# ScannerControlsBreakout.net
KiCad netlist of a schematic drawn in EAGLE
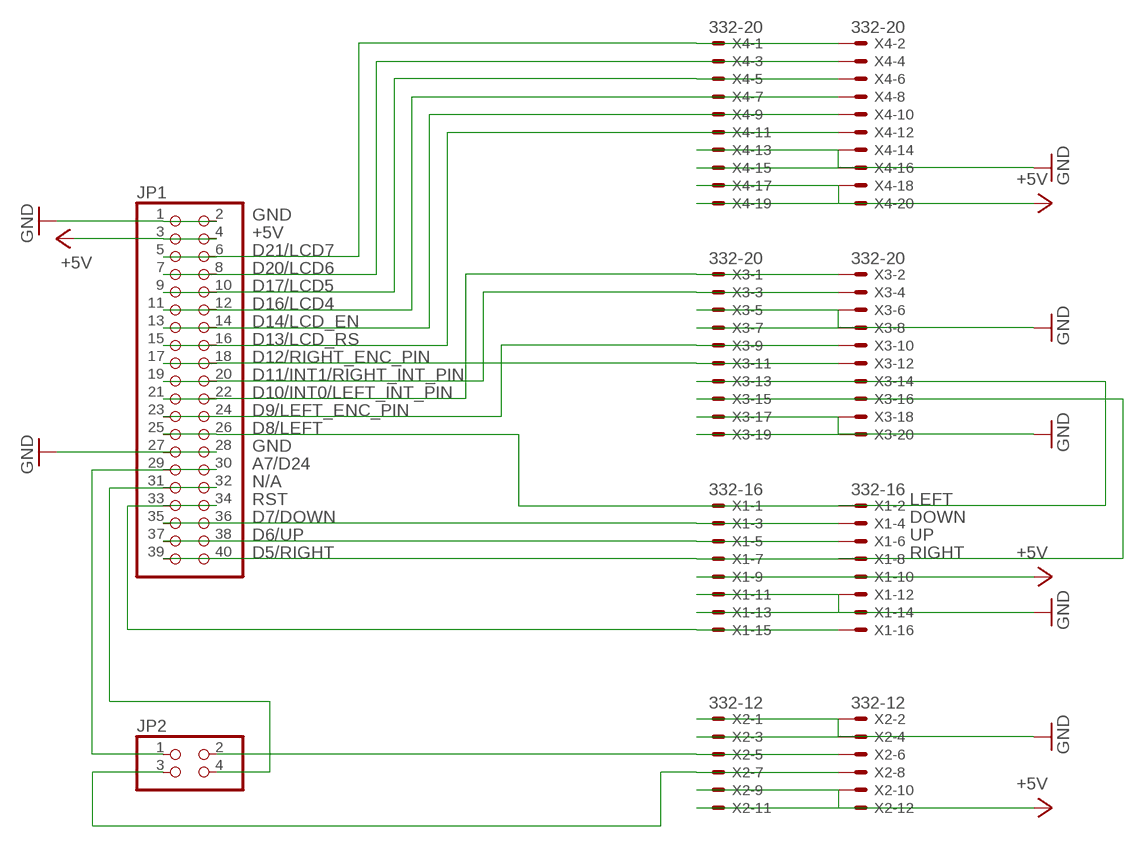
[diagram p0: schematic, sheet 1]

(export (version "E")
  (design (tool "Eeschema 10.0.6"))
  (components
    (comp (ref "JP1")
      (value "PINHD-2X20")
      (footprint "eagle-import:2X20")
      (libsource (lib "eagle-import") (part "PINHD-2X20"))
    )
    (comp (ref "JP2")
      (value "PINHD-2X2")
      (footprint "eagle-import:2X02")
      (libsource (lib "eagle-import") (part "PINHD-2X2"))
    )
    (comp (ref "X1")
      (value "332-16")
      (footprint "eagle-import:332-16")
      (libsource (lib "eagle-import") (part "332-16"))
    )
    (comp (ref "X2")
      (value "332-12")
      (footprint "eagle-import:332-12")
      (libsource (lib "eagle-import") (part "332-12"))
    )
    (comp (ref "X3")
      (value "332-20")
      (footprint "eagle-import:332-20")
      (libsource (lib "eagle-import") (part "332-20"))
    )
    (comp (ref "X4")
      (value "332-20")
      (footprint "eagle-import:332-20")
      (libsource (lib "eagle-import") (part "332-20"))
    )
  )
  (nets
    (net (code "1") (name "+5V") (class "Default")
      (node (ref "JP1") (pin "3") (pinfunction "3_3") (pintype "passive"))
      (node (ref "JP1") (pin "4") (pinfunction "4_4") (pintype "passive"))
      (node (ref "X1") (pin "10") (pinfunction "S_10") (pintype "passive"))
      (node (ref "X1") (pin "9") (pinfunction "S_9") (pintype "passive"))
      (node (ref "X2") (pin "10") (pinfunction "S_10") (pintype "passive"))
      (node (ref "X2") (pin "11") (pinfunction "S_11") (pintype "passive"))
      (node (ref "X2") (pin "12") (pinfunction "S_12") (pintype "passive"))
      (node (ref "X2") (pin "9") (pinfunction "S_9") (pintype "passive"))
      (node (ref "X4") (pin "17") (pinfunction "S_17") (pintype "passive"))
      (node (ref "X4") (pin "18") (pinfunction "S_18") (pintype "passive"))
      (node (ref "X4") (pin "19") (pinfunction "S_19") (pintype "passive"))
      (node (ref "X4") (pin "20") (pinfunction "S_20") (pintype "passive"))
    )
    (net (code "2") (name "GND") (class "Default")
      (node (ref "JP1") (pin "1") (pinfunction "1_1") (pintype "passive"))
      (node (ref "JP1") (pin "2") (pinfunction "2_2") (pintype "passive"))
      (node (ref "JP1") (pin "27") (pinfunction "27_27") (pintype "passive"))
      (node (ref "JP1") (pin "28") (pinfunction "28_28") (pintype "passive"))
      (node (ref "X1") (pin "11") (pinfunction "S_11") (pintype "passive"))
      (node (ref "X1") (pin "12") (pinfunction "S_12") (pintype "passive"))
      (node (ref "X1") (pin "13") (pinfunction "S_13") (pintype "passive"))
      (node (ref "X1") (pin "14") (pinfunction "S_14") (pintype "passive"))
      (node (ref "X2") (pin "1") (pinfunction "S_1") (pintype "passive"))
      (node (ref "X2") (pin "2") (pinfunction "S_2") (pintype "passive"))
      (node (ref "X2") (pin "3") (pinfunction "S_3") (pintype "passive"))
      (node (ref "X2") (pin "4") (pinfunction "S_4") (pintype "passive"))
      (node (ref "X3") (pin "17") (pinfunction "S_17") (pintype "passive"))
      (node (ref "X3") (pin "18") (pinfunction "S_18") (pintype "passive"))
      (node (ref "X3") (pin "19") (pinfunction "S_19") (pintype "passive"))
      (node (ref "X3") (pin "20") (pinfunction "S_20") (pintype "passive"))
      (node (ref "X3") (pin "5") (pinfunction "S_5") (pintype "passive"))
      (node (ref "X3") (pin "6") (pinfunction "S_6") (pintype "passive"))
      (node (ref "X3") (pin "7") (pinfunction "S_7") (pintype "passive"))
      (node (ref "X3") (pin "8") (pinfunction "S_8") (pintype "passive"))
      (node (ref "X4") (pin "13") (pinfunction "S_13") (pintype "passive"))
      (node (ref "X4") (pin "14") (pinfunction "S_14") (pintype "passive"))
      (node (ref "X4") (pin "15") (pinfunction "S_15") (pintype "passive"))
      (node (ref "X4") (pin "16") (pinfunction "S_16") (pintype "passive"))
    )
    (net (code "3") (name "Net-(JP1-Pad29)") (class "Default")
      (node (ref "JP1") (pin "29") (pinfunction "29_29") (pintype "passive"))
      (node (ref "JP1") (pin "30") (pinfunction "30_30") (pintype "passive"))
      (node (ref "JP2") (pin "1") (pinfunction "1_1") (pintype "passive"))
    )
    (net (code "4") (name "Net-(JP1-Pad31)") (class "Default")
      (node (ref "JP1") (pin "31") (pinfunction "31_31") (pintype "passive"))
      (node (ref "JP1") (pin "32") (pinfunction "32_32") (pintype "passive"))
      (node (ref "JP2") (pin "4") (pinfunction "4_4") (pintype "passive"))
    )
    (net (code "5") (name "Net-(X1A-S)") (class "Default")
      (node (ref "JP1") (pin "25") (pinfunction "25_25") (pintype "passive"))
      (node (ref "JP1") (pin "26") (pinfunction "26_26") (pintype "passive"))
      (node (ref "X1") (pin "1") (pinfunction "S_1") (pintype "passive"))
      (node (ref "X1") (pin "2") (pinfunction "S_2") (pintype "passive"))
      (node (ref "X3") (pin "13") (pinfunction "S_13") (pintype "passive"))
      (node (ref "X3") (pin "14") (pinfunction "S_14") (pintype "passive"))
    )
    (net (code "6") (name "Net-(X1G-S)") (class "Default")
      (node (ref "JP1") (pin "33") (pinfunction "33_33") (pintype "passive"))
      (node (ref "JP1") (pin "34") (pinfunction "34_34") (pintype "passive"))
      (node (ref "X1") (pin "15") (pinfunction "S_15") (pintype "passive"))
      (node (ref "X1") (pin "16") (pinfunction "S_16") (pintype "passive"))
    )
    (net (code "7") (name "Net-(X1J-S)") (class "Default")
      (node (ref "JP1") (pin "35") (pinfunction "35_35") (pintype "passive"))
      (node (ref "JP1") (pin "36") (pinfunction "36_36") (pintype "passive"))
      (node (ref "X1") (pin "3") (pinfunction "S_3") (pintype "passive"))
      (node (ref "X1") (pin "4") (pinfunction "S_4") (pintype "passive"))
    )
    (net (code "8") (name "Net-(X1L-S)") (class "Default")
      (node (ref "JP1") (pin "37") (pinfunction "37_37") (pintype "passive"))
      (node (ref "JP1") (pin "38") (pinfunction "38_38") (pintype "passive"))
      (node (ref "X1") (pin "5") (pinfunction "S_5") (pintype "passive"))
      (node (ref "X1") (pin "6") (pinfunction "S_6") (pintype "passive"))
    )
    (net (code "9") (name "Net-(X1N-S)") (class "Default")
      (node (ref "JP1") (pin "39") (pinfunction "39_39") (pintype "passive"))
      (node (ref "JP1") (pin "40") (pinfunction "40_40") (pintype "passive"))
      (node (ref "X1") (pin "7") (pinfunction "S_7") (pintype "passive"))
      (node (ref "X1") (pin "8") (pinfunction "S_8") (pintype "passive"))
      (node (ref "X3") (pin "15") (pinfunction "S_15") (pintype "passive"))
      (node (ref "X3") (pin "16") (pinfunction "S_16") (pintype "passive"))
    )
    (net (code "10") (name "Net-(X2H-S)") (class "Default")
      (node (ref "JP2") (pin "2") (pinfunction "2_2") (pintype "passive"))
      (node (ref "X2") (pin "5") (pinfunction "S_5") (pintype "passive"))
      (node (ref "X2") (pin "6") (pinfunction "S_6") (pintype "passive"))
    )
    (net (code "11") (name "Net-(X2J-S)") (class "Default")
      (node (ref "JP2") (pin "3") (pinfunction "3_3") (pintype "passive"))
      (node (ref "X2") (pin "7") (pinfunction "S_7") (pintype "passive"))
      (node (ref "X2") (pin "8") (pinfunction "S_8") (pintype "passive"))
    )
    (net (code "12") (name "Net-(X3A-S)") (class "Default")
      (node (ref "JP1") (pin "21") (pinfunction "21_21") (pintype "passive"))
      (node (ref "JP1") (pin "22") (pinfunction "22_22") (pintype "passive"))
      (node (ref "X3") (pin "1") (pinfunction "S_1") (pintype "passive"))
      (node (ref "X3") (pin "2") (pinfunction "S_2") (pintype "passive"))
    )
    (net (code "13") (name "Net-(X3B-S)") (class "Default")
      (node (ref "JP1") (pin "23") (pinfunction "23_23") (pintype "passive"))
      (node (ref "JP1") (pin "24") (pinfunction "24_24") (pintype "passive"))
      (node (ref "X3") (pin "10") (pinfunction "S_10") (pintype "passive"))
      (node (ref "X3") (pin "9") (pinfunction "S_9") (pintype "passive"))
    )
    (net (code "14") (name "Net-(X3C-S)") (class "Default")
      (node (ref "JP1") (pin "17") (pinfunction "17_17") (pintype "passive"))
      (node (ref "JP1") (pin "18") (pinfunction "18_18") (pintype "passive"))
      (node (ref "X3") (pin "11") (pinfunction "S_11") (pintype "passive"))
      (node (ref "X3") (pin "12") (pinfunction "S_12") (pintype "passive"))
    )
    (net (code "15") (name "Net-(X3N-S)") (class "Default")
      (node (ref "JP1") (pin "19") (pinfunction "19_19") (pintype "passive"))
      (node (ref "JP1") (pin "20") (pinfunction "20_20") (pintype "passive"))
      (node (ref "X3") (pin "3") (pinfunction "S_3") (pintype "passive"))
      (node (ref "X3") (pin "4") (pinfunction "S_4") (pintype "passive"))
    )
    (net (code "16") (name "Net-(X4A-S)") (class "Default")
      (node (ref "JP1") (pin "5") (pinfunction "5_5") (pintype "passive"))
      (node (ref "JP1") (pin "6") (pinfunction "6_6") (pintype "passive"))
      (node (ref "X4") (pin "1") (pinfunction "S_1") (pintype "passive"))
      (node (ref "X4") (pin "2") (pinfunction "S_2") (pintype "passive"))
    )
    (net (code "17") (name "Net-(X4B-S)") (class "Default")
      (node (ref "JP1") (pin "13") (pinfunction "13_13") (pintype "passive"))
      (node (ref "JP1") (pin "14") (pinfunction "14_14") (pintype "passive"))
      (node (ref "X4") (pin "10") (pinfunction "S_10") (pintype "passive"))
      (node (ref "X4") (pin "9") (pinfunction "S_9") (pintype "passive"))
    )
    (net (code "18") (name "Net-(X4C-S)") (class "Default")
      (node (ref "JP1") (pin "15") (pinfunction "15_15") (pintype "passive"))
      (node (ref "JP1") (pin "16") (pinfunction "16_16") (pintype "passive"))
      (node (ref "X4") (pin "11") (pinfunction "S_11") (pintype "passive"))
      (node (ref "X4") (pin "12") (pinfunction "S_12") (pintype "passive"))
    )
    (net (code "19") (name "Net-(X4N-S)") (class "Default")
      (node (ref "JP1") (pin "7") (pinfunction "7_7") (pintype "passive"))
      (node (ref "JP1") (pin "8") (pinfunction "8_8") (pintype "passive"))
      (node (ref "X4") (pin "3") (pinfunction "S_3") (pintype "passive"))
      (node (ref "X4") (pin "4") (pinfunction "S_4") (pintype "passive"))
    )
    (net (code "20") (name "Net-(X4P-S)") (class "Default")
      (node (ref "JP1") (pin "10") (pinfunction "10_10") (pintype "passive"))
      (node (ref "JP1") (pin "9") (pinfunction "9_9") (pintype "passive"))
      (node (ref "X4") (pin "5") (pinfunction "S_5") (pintype "passive"))
      (node (ref "X4") (pin "6") (pinfunction "S_6") (pintype "passive"))
    )
    (net (code "21") (name "Net-(X4R-S)") (class "Default")
      (node (ref "JP1") (pin "11") (pinfunction "11_11") (pintype "passive"))
      (node (ref "JP1") (pin "12") (pinfunction "12_12") (pintype "passive"))
      (node (ref "X4") (pin "7") (pinfunction "S_7") (pintype "passive"))
      (node (ref "X4") (pin "8") (pinfunction "S_8") (pintype "passive"))
    )
  )
)
